# design.net
KiCad netlist of a schematic drawn in Altium Designer
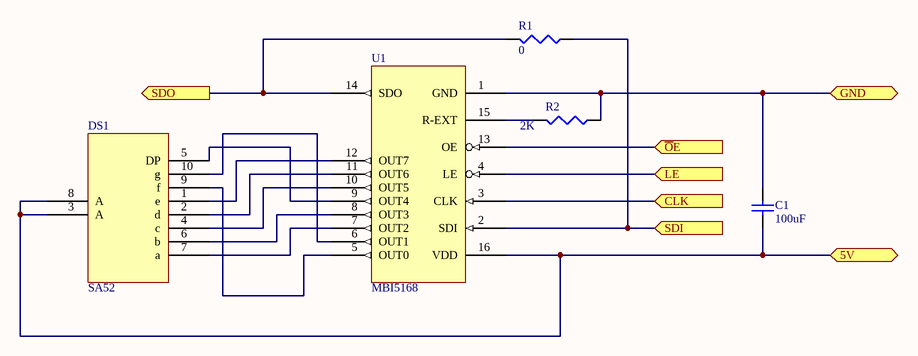
[diagram p0: Индикатор с драйвером.SchDoc]

(export (version "E")
  (design (tool "Eeschema 10.0.6"))
  (components
    (comp (ref "C1")
      (value "100uF")
      (footprint "CAPC1608L")
      (description "Capacitor (Semiconductor SIM Model)")
      (fields (field (name "Comment") "Cap Semi") (field (name "PUBLISHER") "Altium Limited"))
      (libsource (lib "Miscellaneous Devices") (part "Cap Semi"))
    )
    (comp (ref "DS1")
      (value "SA52")
      (footprint "LED52")
      (description "KingBright, SA23-11")
      (libsource (lib "LibX") (part "SA52-11"))
    )
    (comp (ref "R1")
      (value "0")
      (footprint "RESC1608L")
      (description "Resistor")
      (fields (field (name "PUBLISHER") "Altium Limited"))
      (libsource (lib "Miscellaneous Devices") (part "Res3"))
    )
    (comp (ref "R2")
      (value "2K")
      (footprint "RESC1608L")
      (description "Resistor")
      (fields (field (name "Comment") "Res3") (field (name "PUBLISHER") "Altium Limited"))
      (libsource (lib "Miscellaneous Devices") (part "Res3"))
    )
    (comp (ref "U1")
      (value "MBI5168")
      (footprint "SO-16_M")
      (description "Macroblock, 8-bit Constant Current LED Sink Driver")
      (libsource (lib "LibX") (part "MBI5168"))
    )
  )
  (nets
    (net (code "1") (name "/5V") (class "Default")
      (node (ref "C1") (pin "2") (pinfunction "2_2") (pintype "passive"))
      (node (ref "DS1") (pin "3") (pinfunction "A_3") (pintype "passive"))
      (node (ref "DS1") (pin "8") (pinfunction "A_8") (pintype "passive"))
      (node (ref "U1") (pin "16") (pinfunction "VDD_16") (pintype "power_in"))
    )
    (net (code "2") (name "/CLK") (class "Default")
      (node (ref "U1") (pin "3") (pinfunction "CLK_3") (pintype "input"))
    )
    (net (code "3") (name "/GND") (class "Default")
      (node (ref "C1") (pin "1") (pinfunction "1_1") (pintype "passive"))
      (node (ref "R2") (pin "1") (pinfunction "1_1") (pintype "passive"))
      (node (ref "U1") (pin "1") (pinfunction "GND_1") (pintype "power_in"))
    )
    (net (code "4") (name "/LE") (class "Default")
      (node (ref "U1") (pin "4") (pinfunction "LE_4") (pintype "input"))
    )
    (net (code "5") (name "/SDI") (class "Default")
      (node (ref "R1") (pin "1") (pinfunction "1_1") (pintype "passive"))
      (node (ref "U1") (pin "2") (pinfunction "SDI_2") (pintype "input"))
    )
    (net (code "6") (name "/SDO") (class "Default")
      (node (ref "R1") (pin "2") (pinfunction "2_2") (pintype "passive"))
      (node (ref "U1") (pin "14") (pinfunction "SDO_14") (pintype "output"))
    )
    (net (code "7") (name "/~{O}E") (class "Default")
      (node (ref "U1") (pin "13") (pinfunction "OE_13") (pintype "input"))
    )
    (net (code "8") (name "Net-(DS1-DP)") (class "Default")
      (node (ref "DS1") (pin "5") (pinfunction "DP_5") (pintype "passive"))
      (node (ref "U1") (pin "9") (pinfunction "OUT4_9") (pintype "output"))
    )
    (net (code "9") (name "Net-(DS1-a)") (class "Default")
      (node (ref "DS1") (pin "7") (pinfunction "a_7") (pintype "passive"))
      (node (ref "U1") (pin "7") (pinfunction "OUT2_7") (pintype "output"))
    )
    (net (code "10") (name "Net-(DS1-b)") (class "Default")
      (node (ref "DS1") (pin "6") (pinfunction "b_6") (pintype "passive"))
      (node (ref "U1") (pin "8") (pinfunction "OUT3_8") (pintype "output"))
    )
    (net (code "11") (name "Net-(DS1-c)") (class "Default")
      (node (ref "DS1") (pin "4") (pinfunction "c_4") (pintype "passive"))
      (node (ref "U1") (pin "10") (pinfunction "OUT5_10") (pintype "output"))
    )
    (net (code "12") (name "Net-(DS1-d)") (class "Default")
      (node (ref "DS1") (pin "2") (pinfunction "d_2") (pintype "passive"))
      (node (ref "U1") (pin "11") (pinfunction "OUT6_11") (pintype "output"))
    )
    (net (code "13") (name "Net-(DS1-e)") (class "Default")
      (node (ref "DS1") (pin "1") (pinfunction "e_1") (pintype "passive"))
      (node (ref "U1") (pin "12") (pinfunction "OUT7_12") (pintype "output"))
    )
    (net (code "14") (name "Net-(DS1-f)") (class "Default")
      (node (ref "DS1") (pin "9") (pinfunction "f_9") (pintype "passive"))
      (node (ref "U1") (pin "5") (pinfunction "OUT0_5") (pintype "output"))
    )
    (net (code "15") (name "Net-(DS1-g)") (class "Default")
      (node (ref "DS1") (pin "10") (pinfunction "g_10") (pintype "passive"))
      (node (ref "U1") (pin "6") (pinfunction "OUT1_6") (pintype "output"))
    )
    (net (code "16") (name "Net-(U1-R-EXT)") (class "Default")
      (node (ref "R2") (pin "2") (pinfunction "2_2") (pintype "passive"))
      (node (ref "U1") (pin "15") (pinfunction "R-EXT_15") (pintype "passive"))
    )
  )
)
